# AVRControlBoardMain.net
KiCad netlist of a schematic drawn in Altium Designer
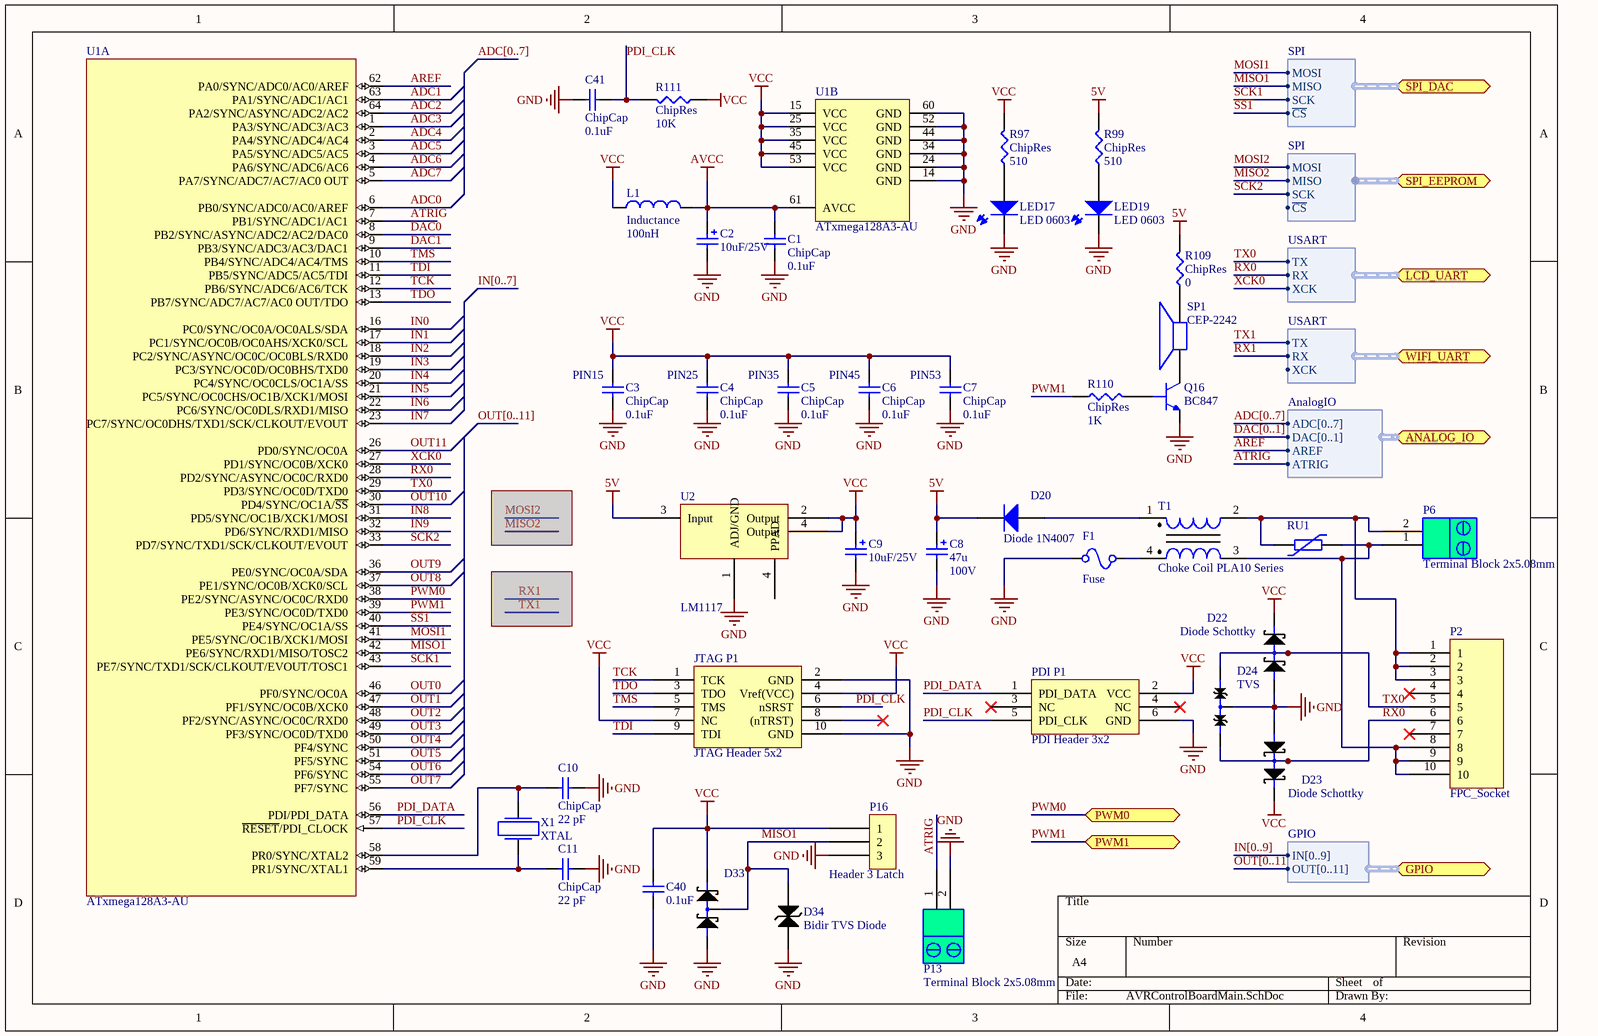
[diagram p0: AVRControlBoardMain.SchDoc]

(export (version "E")
  (design (tool "Eeschema 10.0.6"))
  (components
    (comp (ref "C1")
      (value "ChipCap")
      (footprint "CAP0805")
      (description "Capacitor")
      (fields (field (name "ALTIUM_VALUE") "0.1uF") (field (name "PUBLISHER") "Altium Limited"))
      (libsource (lib "Common Devices") (part "ChipCap"))
    )
    (comp (ref "C2")
      (value "10uF/25V")
      (footprint "CAPC7343")
      (description "Polarized Capacitor (Radial)")
      (fields (field (name "Comment") "Cap Pol SMD"))
      (libsource (lib "Common Devices") (part "Cap Pol Chip"))
    )
    (comp (ref "C3")
      (value "ChipCap")
      (footprint "CAP0805")
      (description "Capacitor")
      (fields (field (name "ALTIUM_VALUE") "0.1uF") (field (name "PUBLISHER") "Altium Limited"))
      (libsource (lib "Common Devices") (part "ChipCap"))
    )
    (comp (ref "C4")
      (value "ChipCap")
      (footprint "CAP0805")
      (description "Capacitor")
      (fields (field (name "ALTIUM_VALUE") "0.1uF") (field (name "PUBLISHER") "Altium Limited"))
      (libsource (lib "Common Devices") (part "ChipCap"))
    )
    (comp (ref "C5")
      (value "ChipCap")
      (footprint "CAP0805")
      (description "Capacitor")
      (fields (field (name "ALTIUM_VALUE") "0.1uF") (field (name "PUBLISHER") "Altium Limited"))
      (libsource (lib "Common Devices") (part "ChipCap"))
    )
    (comp (ref "C6")
      (value "ChipCap")
      (footprint "CAP0805")
      (description "Capacitor")
      (fields (field (name "ALTIUM_VALUE") "0.1uF") (field (name "PUBLISHER") "Altium Limited"))
      (libsource (lib "Common Devices") (part "ChipCap"))
    )
    (comp (ref "C7")
      (value "ChipCap")
      (footprint "CAP0805")
      (description "Capacitor")
      (fields (field (name "ALTIUM_VALUE") "0.1uF") (field (name "PUBLISHER") "Altium Limited"))
      (libsource (lib "Common Devices") (part "ChipCap"))
    )
    (comp (ref "C8")
      (value "47u")
      (footprint "CAPPR5-10x17_1")
      (description "Polarized Capacitor (Radial)")
      (fields (field (name "VOLTAGE") "100V") (field (name "Comment") "Cap Pol 100/47"))
      (libsource (lib "Common Devices") (part "Cap Pol 100/47"))
    )
    (comp (ref "C9")
      (value "10uF/25V")
      (footprint "CAPC7343")
      (description "Polarized Capacitor (Radial)")
      (fields (field (name "Comment") "Cap Pol SMD"))
      (libsource (lib "Common Devices") (part "Cap Pol Chip"))
    )
    (comp (ref "C10")
      (value "ChipCap")
      (footprint "CAP0805")
      (description "Capacitor")
      (fields (field (name "ALTIUM_VALUE") "22 pF") (field (name "PUBLISHER") "Altium Limited"))
      (libsource (lib "Common Devices") (part "ChipCap"))
    )
    (comp (ref "C11")
      (value "ChipCap")
      (footprint "CAP0805")
      (description "Capacitor")
      (fields (field (name "ALTIUM_VALUE") "22 pF") (field (name "PUBLISHER") "Altium Limited"))
      (libsource (lib "Common Devices") (part "ChipCap"))
    )
    (comp (ref "C40")
      (value "0.1uF")
      (footprint "CAP0805")
      (description "Capacitor")
      (fields (field (name "Comment") "ChipCap") (field (name "PUBLISHER") "Altium Limited"))
      (libsource (lib "Common Devices") (part "ChipCap"))
    )
    (comp (ref "C41")
      (value "ChipCap")
      (footprint "CAP0805")
      (description "Capacitor")
      (fields (field (name "ALTIUM_VALUE") "0.1uF") (field (name "PUBLISHER") "Altium Limited"))
      (libsource (lib "Common Devices") (part "ChipCap"))
    )
    (comp (ref "D20")
      (value "Diode 1N4007")
      (footprint "DO-41")
      (description "1 Amp General Purpose Rectifier")
      (fields (field (name "PUBLISHER") "Altium Limited"))
      (libsource (lib "Miscellaneous Devices") (part "Diode 1N4007"))
    )
    (comp (ref "D22")
      (value "Diode Schottky")
      (footprint "SOT23")
      (description "2-Diode Schottky")
      (libsource (lib "Protection") (part "Schottky Diode"))
    )
    (comp (ref "D23")
      (value "Diode Schottky")
      (footprint "SOT23")
      (description "2-Diode Schottky")
      (libsource (lib "") (part "Schottky Diode_1"))
    )
    (comp (ref "D24")
      (value "TVS")
      (footprint "SOT23")
      (description "Dual bidirectional voltage supresor")
      (libsource (lib "Protection") (part "TVS Diode"))
    )
    (comp (ref "D33")
      (value "Diode Schottky")
      (footprint "SOT23")
      (description "2-Diode Schottky")
      (libsource (lib "Protection") (part "Schottky Diode"))
    )
    (comp (ref "D34")
      (value "Bidir TVS Diode")
      (footprint "DO-214AS")
      (libsource (lib "Protection") (part "TVS Bidir Diode SMA"))
    )
    (comp (ref "F1")
      (value "Fuse")
      (footprint "PTC1812")
      (description "Fuse PTC 1812 Thermoresistor")
      (libsource (lib "Protection") (part "Fuse PTC1812"))
    )
    (comp (ref "JTAG P1")
      (value "JTAG Header 5x2")
      (footprint "Header 5x2")
      (description "JTAG Interface connctor")
      (libsource (lib "IndustrialConnectors") (part "JTAG Header 5x2"))
    )
    (comp (ref "L1")
      (value "Inductance")
      (footprint "CM45")
      (fields (field (name "ALTIUM_VALUE") "100nH"))
      (libsource (lib "Common Devices") (part "ChipInductance"))
    )
    (comp (ref "LED17") (value "LED 0603") (footprint "PLCC-2") (libsource (lib "LEDs") (part "LED0603")))
    (comp (ref "LED19") (value "LED 0603") (footprint "PLCC-2") (libsource (lib "LEDs") (part "LED0603")))
    (comp (ref "P2")
      (value "FPC_Socket")
      (footprint "Molex FPC/FFC 10pin")
      (libsource (lib "RibbonConnector") (part "FPC_Socket"))
    )
    (comp (ref "P6")
      (value "Terminal Block 2x5.08mm")
      (footprint "Socket 2x5.08")
      (description "Terminal Block Socket Right Angle 2x5.08mm 2 Wall")
      (libsource (lib "IndustrialConnectors") (part "Socket_2x5.08_RA_2Wall"))
    )
    (comp (ref "P13")
      (value "Terminal Block 2x5.08mm")
      (footprint "Socket 2x5.08")
      (description "Terminal Block Socket Right Angle 2x5.08mm 2 Wall")
      (libsource (lib "") (part "Socket_2x5.08_RA_2Wall_1"))
    )
    (comp (ref "P16")
      (value "Header 3 Latch")
      (footprint "Header 3 latch")
      (description "Header 3 with latch")
      (libsource (lib "IndustrialConnectors") (part "Header 3 latch"))
    )
    (comp (ref "PDI P1")
      (value "PDI Header 3x2")
      (footprint "Header 3x2")
      (description "PDI Interface connector")
      (libsource (lib "IndustrialConnectors") (part "PDI Header 3x2"))
    )
    (comp (ref "Q16")
      (value "BC847")
      (footprint "SOT23")
      (description "NPN transistor")
      (libsource (lib "BJT") (part "BC847"))
    )
    (comp (ref "R97")
      (value "ChipRes")
      (footprint "RES0805")
      (description "Chip resistor")
      (fields (field (name "ALTIUM_VALUE") "510"))
      (libsource (lib "Common Devices") (part "ChipRes"))
    )
    (comp (ref "R99")
      (value "ChipRes")
      (footprint "RES0805")
      (description "Chip resistor")
      (fields (field (name "ALTIUM_VALUE") "510"))
      (libsource (lib "Common Devices") (part "ChipRes"))
    )
    (comp (ref "R109")
      (value "ChipRes")
      (footprint "RES0805")
      (description "Chip resistor")
      (fields (field (name "ALTIUM_VALUE") "0"))
      (libsource (lib "Common Devices") (part "ChipRes"))
    )
    (comp (ref "R110")
      (value "ChipRes")
      (footprint "RES0805")
      (description "Chip resistor")
      (fields (field (name "ALTIUM_VALUE") "1K"))
      (libsource (lib "Common Devices") (part "ChipRes"))
    )
    (comp (ref "R111")
      (value "ChipRes")
      (footprint "RES0805")
      (description "Chip resistor")
      (fields (field (name "ALTIUM_VALUE") "10K"))
      (libsource (lib "Common Devices") (part "ChipRes"))
    )
    (comp (ref "RU1")
      (value "Varistor S14F25")
      (footprint "S14K25")
      (description "varistor")
      (libsource (lib "Protection") (part "Varistor S14K25"))
    )
    (comp (ref "SP1")
      (value "CEP-2242")
      (footprint "Buzzer")
      (description "Buzzer")
      (libsource (lib "Buzzer") (part "Buzzer CEP-2242"))
    )
    (comp (ref "T1")
      (value "Choke Coil PLA10 Series")
      (footprint "PLA10")
      (description "Common Mode Rejection Choke Coil LA10 Series")
      (libsource (lib "Protection") (part "Choke Coil"))
    )
    (comp (ref "U1")
      (value "ATxmega128A3-AU")
      (footprint "64A_L")
      (fields (field (name "PUBLISHER") "Altium Limited"))
      (libsource (lib "Atmel Microcontroller 8-16-Bit AVR XMEGA") (part "ATxmega128A3-AU"))
    )
    (comp (ref "U2")
      (value "LM1117")
      (footprint "SOT223-4M")
      (description "Power Mgt Voltage Regulator")
      (libsource (lib "TI Step Motor Driver") (part "LM1117"))
    )
    (comp (ref "X1")
      (value "XTAL")
      (footprint "BCY-W2/E4.7")
      (description "Quartz crystall oscillator")
      (libsource (lib "Common Devices") (part "Crystall oscillator"))
    )
  )
  (nets
    (net (code "5") (name "/ADC0") (class "Default")
      (node (ref "U1") (pin "6") (pinfunction "PB0/SYNC/ADC0/AC0/AREF_6") (pintype "bidirectional"))
    )
    (net (code "6") (name "/ADC1") (class "Default")
      (node (ref "U1") (pin "63") (pinfunction "PA1/SYNC/ADC1/AC1_63") (pintype "bidirectional"))
    )
    (net (code "7") (name "/ADC2") (class "Default")
      (node (ref "U1") (pin "64") (pinfunction "PA2/SYNC/ASYNC/ADC2/AC2_64") (pintype "bidirectional"))
    )
    (net (code "8") (name "/ADC3") (class "Default")
      (node (ref "U1") (pin "1") (pinfunction "PA3/SYNC/ADC3/AC3_1") (pintype "bidirectional"))
    )
    (net (code "9") (name "/ADC4") (class "Default")
      (node (ref "U1") (pin "2") (pinfunction "PA4/SYNC/ADC4/AC4_2") (pintype "bidirectional"))
    )
    (net (code "10") (name "/ADC5") (class "Default")
      (node (ref "U1") (pin "3") (pinfunction "PA5/SYNC/ADC5/AC5_3") (pintype "bidirectional"))
    )
    (net (code "11") (name "/ADC6") (class "Default")
      (node (ref "U1") (pin "4") (pinfunction "PA6/SYNC/ADC6/AC6_4") (pintype "bidirectional"))
    )
    (net (code "12") (name "/ADC7") (class "Default")
      (node (ref "U1") (pin "5") (pinfunction "PA7/SYNC/ADC7/AC7/AC0_OUT_5") (pintype "bidirectional"))
    )
    (net (code "15") (name "/AREF") (class "Default")
      (node (ref "U1") (pin "62") (pinfunction "PA0/SYNC/ADC0/AC0/AREF_62") (pintype "bidirectional"))
    )
    (net (code "16") (name "/ATRIG") (class "Default")
      (node (ref "P13") (pin "1") (pintype "passive"))
      (node (ref "U1") (pin "7") (pinfunction "PB1/SYNC/ADC1/AC1_7") (pintype "bidirectional"))
    )
    (net (code "17") (name "/DAC0") (class "Default")
      (node (ref "U1") (pin "8") (pinfunction "PB2/SYNC/ASYNC/ADC2/AC2/DAC0_8") (pintype "bidirectional"))
    )
    (net (code "18") (name "/DAC1") (class "Default")
      (node (ref "U1") (pin "9") (pinfunction "PB3/SYNC/ADC3/AC3/DAC1_9") (pintype "bidirectional"))
    )
    (net (code "19") (name "/IN0") (class "Default")
      (node (ref "U1") (pin "16") (pinfunction "PC0/SYNC/OC0A/OC0ALS/SDA_16") (pintype "bidirectional"))
    )
    (net (code "20") (name "/IN1") (class "Default")
      (node (ref "U1") (pin "17") (pinfunction "PC1/SYNC/OC0B/OC0AHS/XCK0/SCL_17") (pintype "bidirectional"))
    )
    (net (code "21") (name "/IN2") (class "Default")
      (node (ref "U1") (pin "18") (pinfunction "PC2/SYNC/ASYNC/OC0C/OC0BLS/RXD0_18") (pintype "bidirectional"))
    )
    (net (code "22") (name "/IN3") (class "Default")
      (node (ref "U1") (pin "19") (pinfunction "PC3/SYNC/OC0D/OC0BHS/TXD0_19") (pintype "bidirectional"))
    )
    (net (code "23") (name "/IN4") (class "Default")
      (node (ref "U1") (pin "20") (pinfunction "PC4/SYNC/OC0CLS/OC1A/SS_20") (pintype "bidirectional"))
    )
    (net (code "24") (name "/IN5") (class "Default")
      (node (ref "U1") (pin "21") (pinfunction "PC5/SYNC/OC0CHS/OC1B/XCK1/MOSI_21") (pintype "bidirectional"))
    )
    (net (code "25") (name "/IN6") (class "Default")
      (node (ref "U1") (pin "22") (pinfunction "PC6/SYNC/OC0DLS/RXD1/MISO_22") (pintype "bidirectional"))
    )
    (net (code "26") (name "/IN7") (class "Default")
      (node (ref "U1") (pin "23") (pinfunction "PC7/SYNC/OC0DHS/TXD1/SCK/CLKOUT/EVOUT_23") (pintype "bidirectional"))
    )
    (net (code "27") (name "/IN8") (class "Default")
      (node (ref "U1") (pin "31") (pinfunction "PD5/SYNC/OC1B/XCK1/MOSI_31") (pintype "bidirectional"))
    )
    (net (code "28") (name "/IN9") (class "Default")
      (node (ref "U1") (pin "32") (pinfunction "PD6/SYNC/RXD1/MISO_32") (pintype "bidirectional"))
    )
    (net (code "31") (name "/MISO1") (class "Default")
      (node (ref "D33") (pin "3") (pinfunction "3_3") (pintype "passive"))
      (node (ref "D34") (pin "1") (pinfunction "1_1") (pintype "passive"))
      (node (ref "P16") (pin "2") (pinfunction "2_2") (pintype "passive"))
      (node (ref "U1") (pin "42") (pinfunction "PE6/SYNC/RXD1/MISO/TOSC2_42") (pintype "bidirectional"))
    )
    (net (code "33") (name "/MOSI1") (class "Default")
      (node (ref "U1") (pin "41") (pinfunction "PE5/SYNC/OC1B/XCK1/MOSI_41") (pintype "bidirectional"))
    )
    (net (code "35") (name "/OUT0") (class "Default")
      (node (ref "U1") (pin "46") (pinfunction "PF0/SYNC/OC0A_46") (pintype "bidirectional"))
    )
    (net (code "36") (name "/OUT1") (class "Default")
      (node (ref "U1") (pin "47") (pinfunction "PF1/SYNC/OC0B/XCK0_47") (pintype "bidirectional"))
    )
    (net (code "37") (name "/OUT2") (class "Default")
      (node (ref "U1") (pin "48") (pinfunction "PF2/SYNC/ASYNC/OC0C/RXD0_48") (pintype "bidirectional"))
    )
    (net (code "38") (name "/OUT3") (class "Default")
      (node (ref "U1") (pin "49") (pinfunction "PF3/SYNC/OC0D/TXD0_49") (pintype "bidirectional"))
    )
    (net (code "39") (name "/OUT4") (class "Default")
      (node (ref "U1") (pin "50") (pinfunction "PF4/SYNC_50") (pintype "bidirectional"))
    )
    (net (code "40") (name "/OUT5") (class "Default")
      (node (ref "U1") (pin "51") (pinfunction "PF5/SYNC_51") (pintype "bidirectional"))
    )
    (net (code "41") (name "/OUT6") (class "Default")
      (node (ref "U1") (pin "54") (pinfunction "PF6/SYNC_54") (pintype "bidirectional"))
    )
    (net (code "42") (name "/OUT7") (class "Default")
      (node (ref "U1") (pin "55") (pinfunction "PF7/SYNC_55") (pintype "bidirectional"))
    )
    (net (code "43") (name "/OUT8") (class "Default")
      (node (ref "U1") (pin "37") (pinfunction "PE1/SYNC/OC0B/XCK0/SCL_37") (pintype "bidirectional"))
    )
    (net (code "44") (name "/OUT9") (class "Default")
      (node (ref "U1") (pin "36") (pinfunction "PE0/SYNC/OC0A/SDA_36") (pintype "bidirectional"))
    )
    (net (code "45") (name "/OUT10") (class "Default")
      (node (ref "U1") (pin "30") (pinfunction "PD4/SYNC/OC1A/~{SS}_30") (pintype "bidirectional"))
    )
    (net (code "46") (name "/OUT11") (class "Default")
      (node (ref "U1") (pin "26") (pinfunction "PD0/SYNC/OC0A_26") (pintype "bidirectional"))
    )
    (net (code "48") (name "/PDI_CLK") (class "Default")
      (node (ref "C41") (pin "2") (pinfunction "2_2") (pintype "passive"))
      (node (ref "JTAG P1") (pin "6") (pinfunction "nSRST_6") (pintype "passive"))
      (node (ref "PDI P1") (pin "5") (pinfunction "PDI_CLK_5") (pintype "passive"))
      (node (ref "R111") (pin "2") (pintype "passive"))
      (node (ref "U1") (pin "57") (pinfunction "~{RESET}/PDI_CLOCK_57") (pintype "input"))
    )
    (net (code "49") (name "/PDI_DATA") (class "Default")
      (node (ref "PDI P1") (pin "1") (pinfunction "PDI_DATA_1") (pintype "passive"))
      (node (ref "U1") (pin "56") (pinfunction "PDI/PDI_DATA_56") (pintype "bidirectional"))
    )
    (net (code "50") (name "/PWM0") (class "Default")
      (node (ref "U1") (pin "38") (pinfunction "PE2/SYNC/ASYNC/OC0C/RXD0_38") (pintype "bidirectional"))
    )
    (net (code "51") (name "/PWM1") (class "Default")
      (node (ref "R110") (pin "1") (pintype "passive"))
      (node (ref "U1") (pin "39") (pinfunction "PE3/SYNC/OC0D/TXD0_39") (pintype "bidirectional"))
    )
    (net (code "52") (name "/RX0") (class "Default")
      (node (ref "D23") (pin "3") (pinfunction "3_3") (pintype "passive"))
      (node (ref "D24") (pin "2") (pinfunction "2_2") (pintype "passive"))
      (node (ref "P2") (pin "6") (pinfunction "6_6") (pintype "passive"))
      (node (ref "U1") (pin "28") (pinfunction "PD2/SYNC/ASYNC/OC0C/RXD0_28") (pintype "bidirectional"))
    )
    (net (code "54") (name "/SCK1") (class "Default")
      (node (ref "U1") (pin "43") (pinfunction "PE7/SYNC/TXD1/SCK/CLKOUT/EVOUT/TOSC1_43") (pintype "bidirectional"))
    )
    (net (code "55") (name "/SCK2") (class "Default")
      (node (ref "U1") (pin "33") (pinfunction "PD7/SYNC/TXD1/SCK/CLKOUT/EVOUT_33") (pintype "bidirectional"))
    )
    (net (code "56") (name "/TCK") (class "Default")
      (node (ref "JTAG P1") (pin "1") (pinfunction "TCK_1") (pintype "passive"))
      (node (ref "U1") (pin "12") (pinfunction "PB6/SYNC/ADC6/AC6/TCK_12") (pintype "bidirectional"))
    )
    (net (code "57") (name "/TDI") (class "Default")
      (node (ref "JTAG P1") (pin "9") (pinfunction "TDI_9") (pintype "passive"))
      (node (ref "U1") (pin "11") (pinfunction "PB5/SYNC/ADC5/AC5/TDI_11") (pintype "bidirectional"))
    )
    (net (code "58") (name "/TDO") (class "Default")
      (node (ref "JTAG P1") (pin "3") (pinfunction "TDO_3") (pintype "passive"))
      (node (ref "U1") (pin "13") (pinfunction "PB7/SYNC/ADC7/AC7/AC0_OUT/TDO_13") (pintype "bidirectional"))
    )
    (net (code "59") (name "/TMS") (class "Default")
      (node (ref "JTAG P1") (pin "5") (pinfunction "TMS_5") (pintype "passive"))
      (node (ref "U1") (pin "10") (pinfunction "PB4/SYNC/ADC4/AC4/TMS_10") (pintype "bidirectional"))
    )
    (net (code "60") (name "/TX0") (class "Default")
      (node (ref "D22") (pin "3") (pinfunction "3_3") (pintype "passive"))
      (node (ref "D24") (pin "1") (pinfunction "1_1") (pintype "passive"))
      (node (ref "P2") (pin "5") (pinfunction "5_5") (pintype "passive"))
      (node (ref "U1") (pin "29") (pinfunction "PD3/SYNC/OC0D/TXD0_29") (pintype "bidirectional"))
    )
    (net (code "62") (name "/XCK0") (class "Default")
      (node (ref "U1") (pin "27") (pinfunction "PD1/SYNC/OC0B/XCK0_27") (pintype "bidirectional"))
    )
    (net (code "67") (name "/~{SS1}") (class "Default")
      (node (ref "U1") (pin "40") (pinfunction "PE4/SYNC/OC1A/SS_40") (pintype "bidirectional"))
    )
    (net (code "68") (name "5V") (class "Default")
      (node (ref "C8") (pin "1") (pinfunction "1_1") (pintype "passive"))
      (node (ref "D20") (pin "2") (pinfunction "K_2") (pintype "passive"))
      (node (ref "R109") (pin "2") (pintype "passive"))
      (node (ref "R99") (pin "2") (pintype "passive"))
      (node (ref "U2") (pin "3") (pinfunction "Input_3") (pintype "power_in"))
    )
    (net (code "69") (name "AVCC") (class "Default")
      (node (ref "C1") (pin "2") (pinfunction "2_2") (pintype "passive"))
      (node (ref "C2") (pin "1") (pinfunction "1_1") (pintype "passive"))
      (node (ref "L1") (pin "1") (pintype "passive"))
      (node (ref "U1") (pin "61") (pinfunction "AVCC_61") (pintype "power_in"))
    )
    (net (code "70") (name "GND") (class "Default")
      (node (ref "C1") (pin "1") (pinfunction "1_1") (pintype "passive"))
      (node (ref "C10") (pin "1") (pinfunction "1_1") (pintype "passive"))
      (node (ref "C11") (pin "1") (pinfunction "1_1") (pintype "passive"))
      (node (ref "C2") (pin "2") (pinfunction "2_2") (pintype "passive"))
      (node (ref "C3") (pin "1") (pinfunction "1_1") (pintype "passive"))
      (node (ref "C4") (pin "1") (pinfunction "1_1") (pintype "passive"))
      (node (ref "C40") (pin "2") (pinfunction "2_2") (pintype "passive"))
      (node (ref "C41") (pin "1") (pinfunction "1_1") (pintype "passive"))
      (node (ref "C5") (pin "1") (pinfunction "1_1") (pintype "passive"))
      (node (ref "C6") (pin "1") (pinfunction "1_1") (pintype "passive"))
      (node (ref "C7") (pin "1") (pinfunction "1_1") (pintype "passive"))
      (node (ref "C8") (pin "2") (pinfunction "2_2") (pintype "passive"))
      (node (ref "C9") (pin "2") (pinfunction "2_2") (pintype "passive"))
      (node (ref "D22") (pin "1") (pinfunction "1_1") (pintype "passive"))
      (node (ref "D23") (pin "1") (pinfunction "1_1") (pintype "passive"))
      (node (ref "D24") (pin "3") (pinfunction "3_3") (pintype "passive"))
      (node (ref "D33") (pin "1") (pinfunction "1_1") (pintype "passive"))
      (node (ref "D34") (pin "2") (pinfunction "2_2") (pintype "passive"))
      (node (ref "F1") (pin "1") (pinfunction "1_1") (pintype "passive"))
      (node (ref "JTAG P1") (pin "10") (pinfunction "GND_10") (pintype "passive"))
      (node (ref "JTAG P1") (pin "2") (pinfunction "GND_2") (pintype "passive"))
      (node (ref "LED17") (pin "1") (pinfunction "1_1") (pintype "passive"))
      (node (ref "LED19") (pin "1") (pinfunction "1_1") (pintype "passive"))
      (node (ref "P13") (pin "2") (pintype "passive"))
      (node (ref "P16") (pin "3") (pinfunction "3_3") (pintype "passive"))
      (node (ref "PDI P1") (pin "6") (pinfunction "GND_6") (pintype "passive"))
      (node (ref "Q16") (pin "2") (pinfunction "2_2") (pintype "passive"))
      (node (ref "U1") (pin "14") (pinfunction "GND_14") (pintype "power_in"))
      (node (ref "U1") (pin "24") (pinfunction "GND_24") (pintype "power_in"))
      (node (ref "U1") (pin "34") (pinfunction "GND_34") (pintype "power_in"))
      (node (ref "U1") (pin "44") (pinfunction "GND_44") (pintype "power_in"))
      (node (ref "U1") (pin "52") (pinfunction "GND_52") (pintype "power_in"))
      (node (ref "U1") (pin "60") (pinfunction "GND_60") (pintype "power_in"))
      (node (ref "U2") (pin "1") (pinfunction "ADJ/GND_1") (pintype "power_in"))
    )
    (net (code "71") (name "Net-(D20-A)") (class "Default")
      (node (ref "D20") (pin "1") (pinfunction "A_1") (pintype "passive"))
      (node (ref "T1") (pin "1") (pinfunction "1_1") (pintype "passive"))
    )
    (net (code "72") (name "Net-(F1-Pad2)") (class "Default")
      (node (ref "F1") (pin "2") (pinfunction "2_2") (pintype "passive"))
      (node (ref "T1") (pin "4") (pinfunction "4_4") (pintype "passive"))
    )
    (net (code "73") (name "Net-(LED17-Pad2)") (class "Default")
      (node (ref "LED17") (pin "2") (pinfunction "2_2") (pintype "passive"))
      (node (ref "R97") (pin "1") (pintype "passive"))
    )
    (net (code "74") (name "Net-(LED19-Pad2)") (class "Default")
      (node (ref "LED19") (pin "2") (pinfunction "2_2") (pintype "passive"))
      (node (ref "R99") (pin "1") (pintype "passive"))
    )
    (net (code "75") (name "Net-(P2-Pad1)") (class "Default")
      (node (ref "P2") (pin "1") (pinfunction "1_1") (pintype "passive"))
      (node (ref "P2") (pin "2") (pinfunction "2_2") (pintype "passive"))
      (node (ref "P2") (pin "3") (pinfunction "3_3") (pintype "passive"))
      (node (ref "P6") (pin "2") (pintype "passive"))
      (node (ref "RU1") (pin "1") (pinfunction "1_1") (pintype "passive"))
      (node (ref "T1") (pin "2") (pinfunction "2_2") (pintype "passive"))
    )
    (net (code "76") (name "Net-(P2-Pad10)") (class "Default")
      (node (ref "P2") (pin "10") (pinfunction "10_10") (pintype "passive"))
      (node (ref "P2") (pin "8") (pinfunction "8_8") (pintype "passive"))
      (node (ref "P2") (pin "9") (pinfunction "9_9") (pintype "passive"))
      (node (ref "P6") (pin "1") (pintype "passive"))
      (node (ref "RU1") (pin "2") (pinfunction "2_2") (pintype "passive"))
      (node (ref "T1") (pin "3") (pinfunction "3_3") (pintype "passive"))
    )
    (net (code "77") (name "Net-(Q16-Pad1)") (class "Default")
      (node (ref "Q16") (pin "1") (pinfunction "1_1") (pintype "passive"))
      (node (ref "R110") (pin "2") (pintype "passive"))
    )
    (net (code "78") (name "Net-(Q16-Pad3)") (class "Default")
      (node (ref "Q16") (pin "3") (pinfunction "3_3") (pintype "passive"))
      (node (ref "SP1") (pin "1") (pinfunction "1_1") (pintype "passive"))
    )
    (net (code "79") (name "Net-(R109-Pad1)") (class "Default")
      (node (ref "R109") (pin "1") (pintype "passive"))
      (node (ref "SP1") (pin "2") (pinfunction "2_2") (pintype "passive"))
    )
    (net (code "80") (name "Net-(U1A-PR0{slash}SYNC{slash}XTAL2)") (class "Default")
      (node (ref "C10") (pin "2") (pinfunction "2_2") (pintype "passive"))
      (node (ref "U1") (pin "58") (pinfunction "PR0/SYNC/XTAL2_58") (pintype "bidirectional"))
      (node (ref "X1") (pin "2") (pinfunction "2_2") (pintype "passive"))
    )
    (net (code "81") (name "Net-(U1A-PR1{slash}SYNC{slash}XTAL1)") (class "Default")
      (node (ref "C11") (pin "2") (pinfunction "2_2") (pintype "passive"))
      (node (ref "U1") (pin "59") (pinfunction "PR1/SYNC/XTAL1_59") (pintype "bidirectional"))
      (node (ref "X1") (pin "1") (pinfunction "1_1") (pintype "passive"))
    )
    (net (code "82") (name "VCC") (class "Default")
      (node (ref "C3") (pin "2") (pinfunction "2_2") (pintype "passive"))
      (node (ref "C4") (pin "2") (pinfunction "2_2") (pintype "passive"))
      (node (ref "C40") (pin "1") (pinfunction "1_1") (pintype "passive"))
      (node (ref "C5") (pin "2") (pinfunction "2_2") (pintype "passive"))
      (node (ref "C6") (pin "2") (pinfunction "2_2") (pintype "passive"))
      (node (ref "C7") (pin "2") (pinfunction "2_2") (pintype "passive"))
      (node (ref "C9") (pin "1") (pinfunction "1_1") (pintype "passive"))
      (node (ref "D22") (pin "2") (pinfunction "2_2") (pintype "passive"))
      (node (ref "D23") (pin "2") (pinfunction "2_2") (pintype "passive"))
      (node (ref "D33") (pin "2") (pinfunction "2_2") (pintype "passive"))
      (node (ref "JTAG P1") (pin "4") (pinfunction "Vref(VCC)_4") (pintype "passive"))
      (node (ref "JTAG P1") (pin "7") (pinfunction "NC_7") (pintype "passive"))
      (node (ref "L1") (pin "2") (pintype "passive"))
      (node (ref "P16") (pin "1") (pinfunction "1_1") (pintype "passive"))
      (node (ref "PDI P1") (pin "2") (pinfunction "VCC_2") (pintype "passive"))
      (node (ref "R111") (pin "1") (pintype "passive"))
      (node (ref "R97") (pin "2") (pintype "passive"))
      (node (ref "U1") (pin "15") (pinfunction "VCC_15") (pintype "power_in"))
      (node (ref "U1") (pin "25") (pinfunction "VCC_25") (pintype "power_in"))
      (node (ref "U1") (pin "35") (pinfunction "VCC_35") (pintype "power_in"))
      (node (ref "U1") (pin "45") (pinfunction "VCC_45") (pintype "power_in"))
      (node (ref "U1") (pin "53") (pinfunction "VCC_53") (pintype "power_in"))
      (node (ref "U2") (pin "2") (pinfunction "Output_2") (pintype "power_in"))
      (node (ref "U2") (pin "4") (pinfunction "Output_4") (pintype "power_in"))
    )
    (net (code "83") (name "unconnected-(JTAG P1-(nTRST)-Pad8)") (class "Default")
      (node (ref "JTAG P1") (pin "8") (pinfunction "(nTRST)_8") (pintype "passive+no_connect"))
    )
    (net (code "84") (name "unconnected-(P2-Pad4)") (class "Default")
      (node (ref "P2") (pin "4") (pinfunction "4_4") (pintype "passive+no_connect"))
    )
    (net (code "85") (name "unconnected-(P2-Pad7)") (class "Default")
      (node (ref "P2") (pin "7") (pinfunction "7_7") (pintype "passive+no_connect"))
    )
    (net (code "86") (name "unconnected-(PDI P1-NC-Pad3)") (class "Default")
      (node (ref "PDI P1") (pin "3") (pinfunction "NC_3") (pintype "passive+no_connect"))
    )
    (net (code "87") (name "unconnected-(PDI P1-NC-Pad4)") (class "Default")
      (node (ref "PDI P1") (pin "4") (pinfunction "NC_4") (pintype "passive+no_connect"))
    )
    (net (code "88") (name "unconnected-(U2-PPAD-Pad4)") (class "Default")
      (node (ref "U2") (pin "4") (pinfunction "PPAD_4") (pintype "passive"))
    )
  )
)
